# Amplifier.net
KiCad netlist of a schematic drawn in Altium Designer
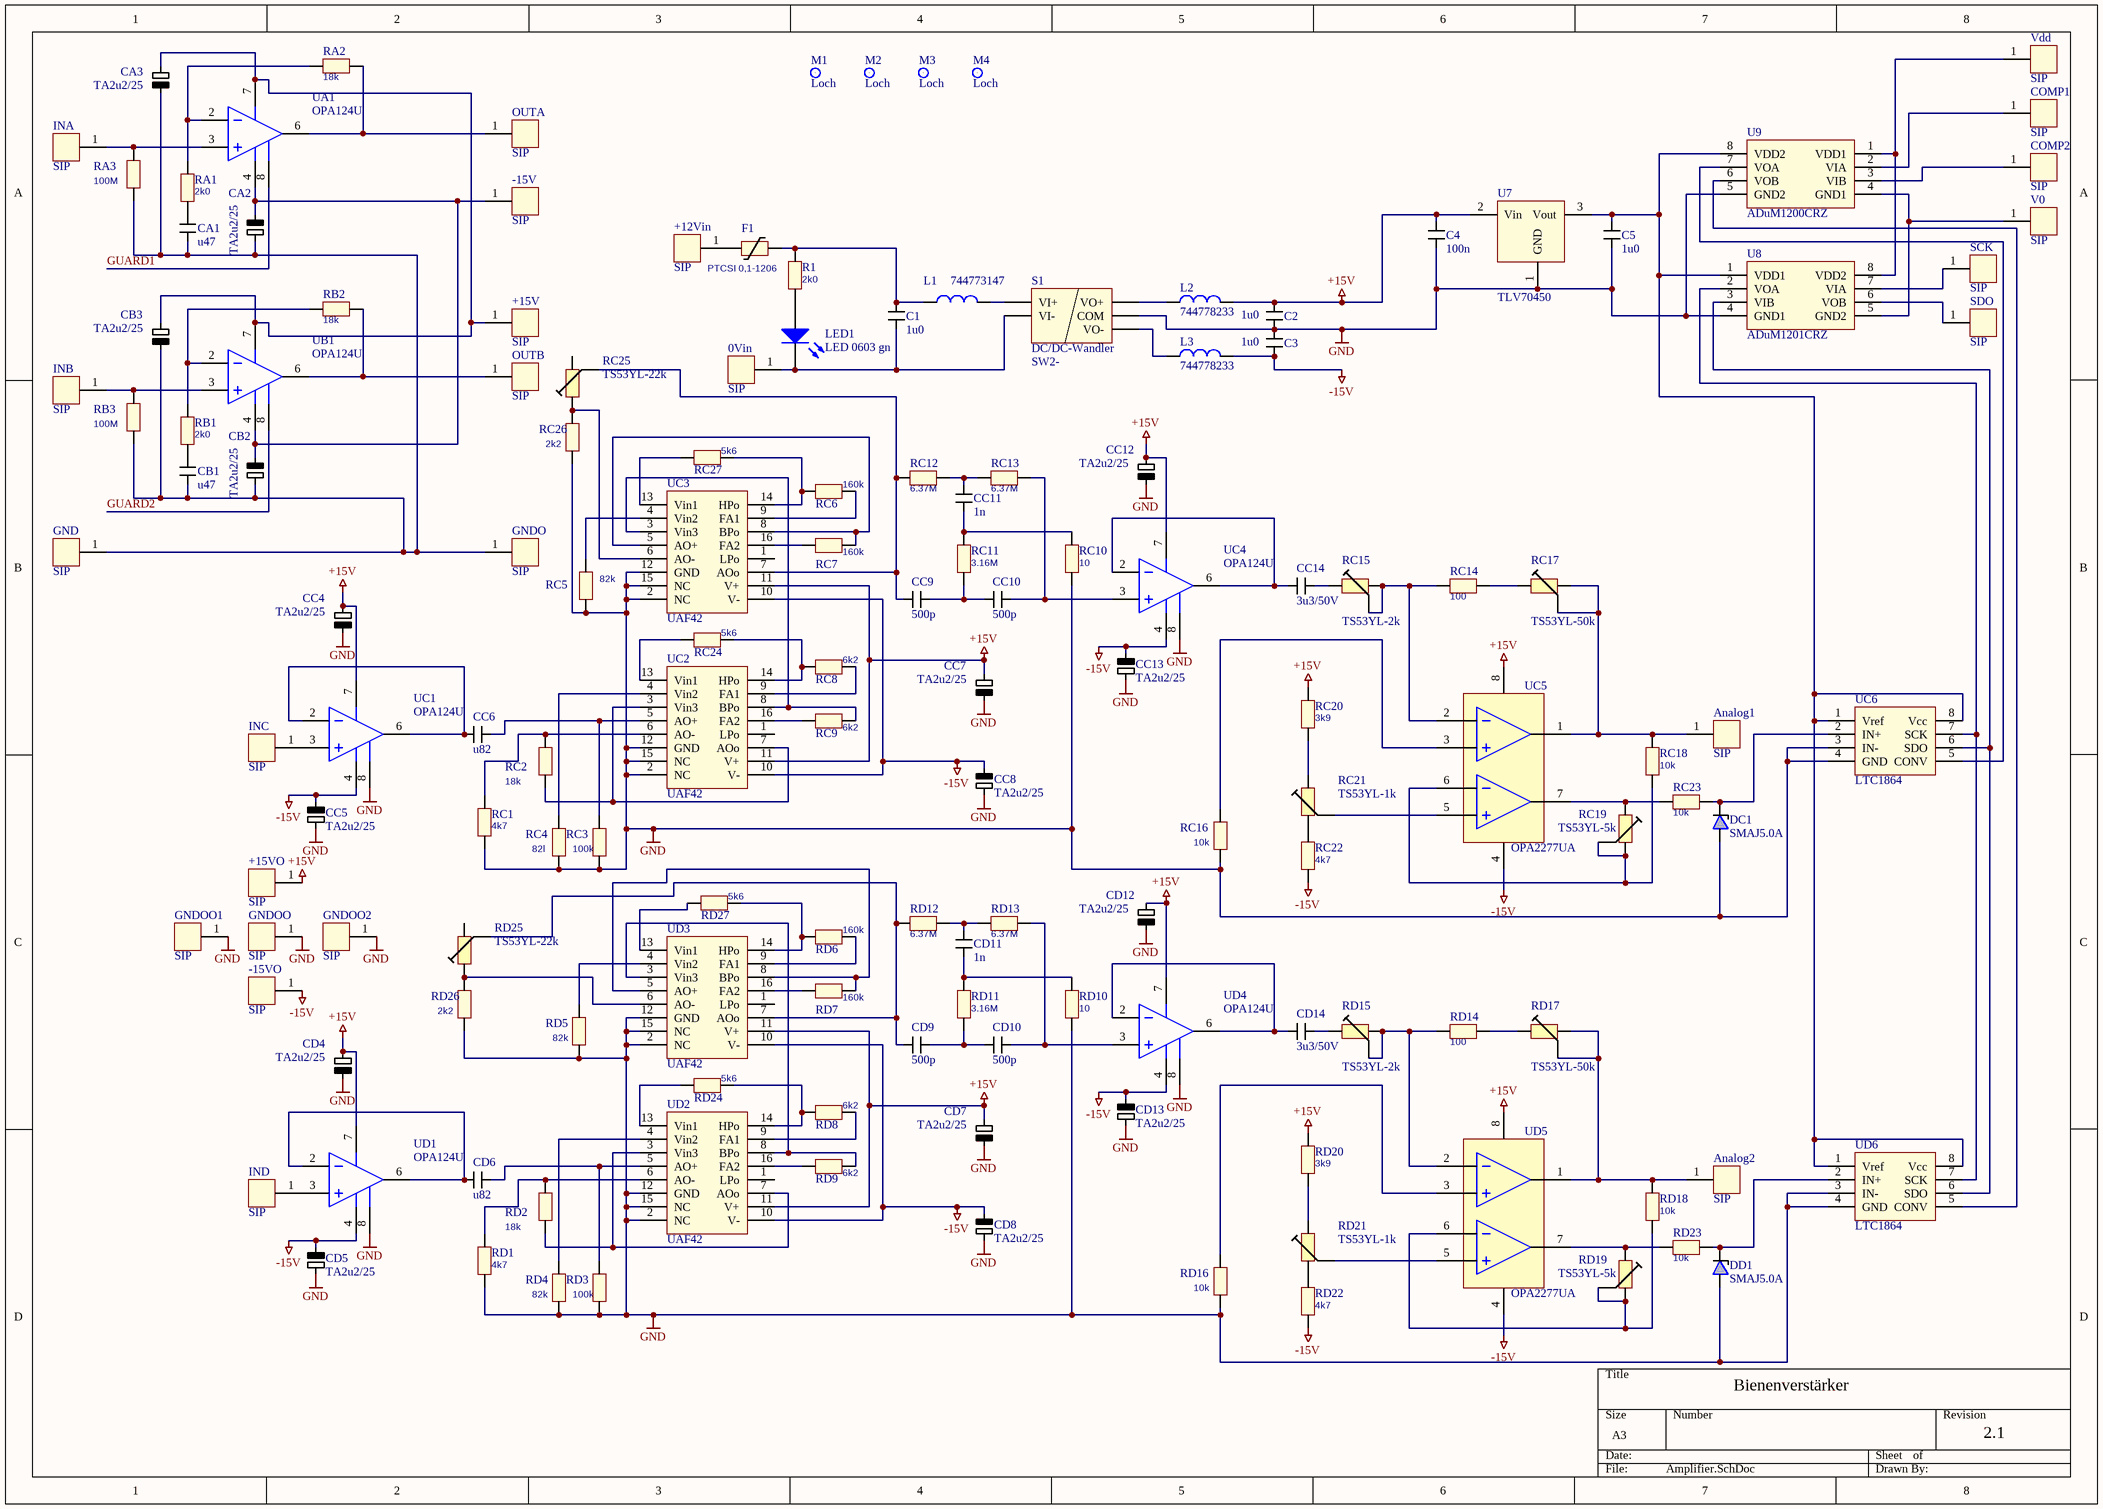
[diagram p0: Amplifier.SchDoc]

(export (version "E")
  (design (tool "Eeschema 10.0.6"))
  (components
    (comp (ref "+12Vin")
      (value "SIP")
      (footprint "PAD2,2x2,5")
      (description "2-pol. Leiste")
      (libsource (lib "") (part "SIP1_1"))
    )
    (comp (ref "+15V")
      (value "SIP")
      (footprint "PAD1X1")
      (description "2-pol. Leiste")
      (libsource (lib "GEP_EMech") (part "SIP1"))
    )
    (comp (ref "+15VO")
      (value "SIP")
      (footprint "PAD2,2x2,5")
      (description "2-pol. Leiste")
      (libsource (lib "") (part "SIP1_2"))
    )
    (comp (ref "-15V")
      (value "SIP")
      (footprint "PAD1X1")
      (description "2-pol. Leiste")
      (libsource (lib "GEP_EMech") (part "SIP1"))
    )
    (comp (ref "-15VO")
      (value "SIP")
      (footprint "PAD2,2x2,5")
      (description "2-pol. Leiste")
      (libsource (lib "") (part "SIP1_2"))
    )
    (comp (ref "0Vin")
      (value "SIP")
      (footprint "PAD2,2x2,5")
      (description "2-pol. Leiste")
      (libsource (lib "") (part "SIP1_1"))
    )
    (comp (ref "Analog1")
      (value "SIP")
      (footprint "PAD2,2x2,5")
      (description "2-pol. Leiste")
      (libsource (lib "GEP_EMech") (part "SIP1"))
    )
    (comp (ref "Analog2")
      (value "SIP")
      (footprint "PAD2,2x2,5")
      (description "2-pol. Leiste")
      (libsource (lib "GEP_EMech") (part "SIP1"))
    )
    (comp (ref "C1")
      (value "1u0")
      (footprint "0603")
      (description "Capacitor")
      (libsource (lib "GEP_Passiv") (part "Capacitor"))
    )
    (comp (ref "C2")
      (value "1u0")
      (footprint "0603")
      (description "Capacitor")
      (libsource (lib "GEP_Passiv") (part "Capacitor"))
    )
    (comp (ref "C3")
      (value "1u0")
      (footprint "0603")
      (description "Capacitor")
      (libsource (lib "GEP_Passiv") (part "Capacitor"))
    )
    (comp (ref "C4")
      (value "100n")
      (footprint "0603")
      (description "Capacitor")
      (libsource (lib "GEP_Passiv") (part "Capacitor"))
    )
    (comp (ref "C5")
      (value "1u0")
      (footprint "0603")
      (description "Capacitor")
      (libsource (lib "GEP_Passiv") (part "Capacitor"))
    )
    (comp (ref "CA1")
      (value "u47")
      (footprint "0603")
      (description "Capacitor")
      (libsource (lib "GEP_Passiv") (part "Capacitor"))
    )
    (comp (ref "CA2")
      (value "TA2u2/25")
      (footprint "TA_SMD-A")
      (description "Elko")
      (libsource (lib "GEP_Passiv") (part "Elko"))
    )
    (comp (ref "CA3")
      (value "TA2u2/25")
      (footprint "TA_SMD-A")
      (description "Elko")
      (libsource (lib "") (part "Elko_1"))
    )
    (comp (ref "CB1")
      (value "u47")
      (footprint "0603")
      (description "Capacitor")
      (libsource (lib "GEP_Passiv") (part "Capacitor"))
    )
    (comp (ref "CB2")
      (value "TA2u2/25")
      (footprint "TA_SMD-A")
      (description "Elko")
      (libsource (lib "GEP_Passiv") (part "Elko"))
    )
    (comp (ref "CB3")
      (value "TA2u2/25")
      (footprint "TA_SMD-A")
      (description "Elko")
      (libsource (lib "") (part "Elko_1"))
    )
    (comp (ref "CC4")
      (value "TA2u2/25")
      (footprint "TA_SMD-A")
      (description "Elko")
      (libsource (lib "") (part "Elko_1"))
    )
    (comp (ref "CC5")
      (value "TA2u2/25")
      (footprint "TA_SMD-A")
      (description "Elko")
      (libsource (lib "GEP_Passiv") (part "Elko"))
    )
    (comp (ref "CC6")
      (value "u82")
      (footprint "C0805")
      (description "Capacitor")
      (libsource (lib "GEP_Passiv") (part "Capacitor"))
    )
    (comp (ref "CC7")
      (value "TA2u2/25")
      (footprint "TA_SMD-A")
      (description "Elko")
      (libsource (lib "") (part "Elko_1"))
    )
    (comp (ref "CC8")
      (value "TA2u2/25")
      (footprint "TA_SMD-A")
      (description "Elko")
      (libsource (lib "GEP_Passiv") (part "Elko"))
    )
    (comp (ref "CC9")
      (value "500p")
      (footprint "0603")
      (description "Capacitor")
      (libsource (lib "GEP_Passiv") (part "Capacitor"))
    )
    (comp (ref "CC10")
      (value "500p")
      (footprint "0603")
      (description "Capacitor")
      (libsource (lib "GEP_Passiv") (part "Capacitor"))
    )
    (comp (ref "CC11")
      (value "1n")
      (footprint "0603")
      (description "Capacitor")
      (libsource (lib "GEP_Passiv") (part "Capacitor"))
    )
    (comp (ref "CC12")
      (value "TA2u2/25")
      (footprint "TA_SMD-A")
      (description "Elko")
      (libsource (lib "") (part "Elko_1"))
    )
    (comp (ref "CC13")
      (value "TA2u2/25")
      (footprint "TA_SMD-A")
      (description "Elko")
      (libsource (lib "GEP_Passiv") (part "Elko"))
    )
    (comp (ref "CC14")
      (value "3u3/50V")
      (footprint "1206")
      (description "Capacitor")
      (libsource (lib "GEP_Passiv") (part "Capacitor"))
    )
    (comp (ref "CD4")
      (value "TA2u2/25")
      (footprint "TA_SMD-A")
      (description "Elko")
      (libsource (lib "") (part "Elko_1"))
    )
    (comp (ref "CD5")
      (value "TA2u2/25")
      (footprint "TA_SMD-A")
      (description "Elko")
      (libsource (lib "GEP_Passiv") (part "Elko"))
    )
    (comp (ref "CD6")
      (value "u82")
      (footprint "C0805")
      (description "Capacitor")
      (libsource (lib "GEP_Passiv") (part "Capacitor"))
    )
    (comp (ref "CD7")
      (value "TA2u2/25")
      (footprint "TA_SMD-A")
      (description "Elko")
      (libsource (lib "") (part "Elko_1"))
    )
    (comp (ref "CD8")
      (value "TA2u2/25")
      (footprint "TA_SMD-A")
      (description "Elko")
      (libsource (lib "GEP_Passiv") (part "Elko"))
    )
    (comp (ref "CD9")
      (value "500p")
      (footprint "0603")
      (description "Capacitor")
      (libsource (lib "GEP_Passiv") (part "Capacitor"))
    )
    (comp (ref "CD10")
      (value "500p")
      (footprint "0603")
      (description "Capacitor")
      (libsource (lib "GEP_Passiv") (part "Capacitor"))
    )
    (comp (ref "CD11")
      (value "1n")
      (footprint "0603")
      (description "Capacitor")
      (libsource (lib "GEP_Passiv") (part "Capacitor"))
    )
    (comp (ref "CD12")
      (value "TA2u2/25")
      (footprint "TA_SMD-A")
      (description "Elko")
      (libsource (lib "") (part "Elko_1"))
    )
    (comp (ref "CD13")
      (value "TA2u2/25")
      (footprint "TA_SMD-A")
      (description "Elko")
      (libsource (lib "GEP_Passiv") (part "Elko"))
    )
    (comp (ref "CD14")
      (value "3u3/50V")
      (footprint "1206")
      (description "Capacitor")
      (libsource (lib "GEP_Passiv") (part "Capacitor"))
    )
    (comp (ref "COMP1")
      (value "SIP")
      (footprint "PAD2,2x2,5")
      (description "2-pol. Leiste")
      (libsource (lib "GEP_EMech") (part "SIP1"))
    )
    (comp (ref "COMP2")
      (value "SIP")
      (footprint "PAD2,2x2,5")
      (description "2-pol. Leiste")
      (libsource (lib "GEP_EMech") (part "SIP1"))
    )
    (comp (ref "DC1")
      (value "SMAJ5.0A")
      (footprint "SMA (DO214AC)")
      (description "DIODE TRANSIL")
      (libsource (lib "GEP_Discrete") (part "DIODE TRANSIL"))
    )
    (comp (ref "DD1")
      (value "SMAJ5.0A")
      (footprint "SMA (DO214AC)")
      (description "DIODE TRANSIL")
      (libsource (lib "GEP_Discrete") (part "DIODE TRANSIL"))
    )
    (comp (ref "F1")
      (value "PTCSI 0,1-1206")
      (footprint "1206")
      (description "Multifuse")
      (libsource (lib "GEP_Passiv") (part "Multifuse"))
    )
    (comp (ref "GND")
      (value "SIP")
      (footprint "PAD1X1")
      (description "2-pol. Leiste")
      (libsource (lib "") (part "SIP1_2"))
    )
    (comp (ref "GNDO")
      (value "SIP")
      (footprint "PAD1X1")
      (description "2-pol. Leiste")
      (libsource (lib "GEP_EMech") (part "SIP1"))
    )
    (comp (ref "GNDOO")
      (value "SIP")
      (footprint "PAD2,2x2,5")
      (description "2-pol. Leiste")
      (libsource (lib "") (part "SIP1_2"))
    )
    (comp (ref "GNDOO1")
      (value "SIP")
      (footprint "PAD2,2x2,5")
      (description "2-pol. Leiste")
      (libsource (lib "") (part "SIP1_2"))
    )
    (comp (ref "GNDOO2")
      (value "SIP")
      (footprint "PAD2,2x2,5")
      (description "2-pol. Leiste")
      (libsource (lib "") (part "SIP1_2"))
    )
    (comp (ref "INA")
      (value "SIP")
      (footprint "PAD1X1")
      (description "2-pol. Leiste")
      (libsource (lib "") (part "SIP1_2"))
    )
    (comp (ref "INB")
      (value "SIP")
      (footprint "PAD1X1")
      (description "2-pol. Leiste")
      (libsource (lib "") (part "SIP1_2"))
    )
    (comp (ref "INC")
      (value "SIP")
      (footprint "PAD2,2x2,5")
      (description "2-pol. Leiste")
      (libsource (lib "") (part "SIP1_2"))
    )
    (comp (ref "IND")
      (value "SIP")
      (footprint "PAD2,2x2,5")
      (description "2-pol. Leiste")
      (libsource (lib "") (part "SIP1_2"))
    )
    (comp (ref "L1")
      (value "744773147")
      (footprint "WE-4045")
      (description "Inductor")
      (libsource (lib "GEP_Passiv") (part "Inductor"))
    )
    (comp (ref "L2")
      (value "744778233")
      (footprint "WE-PD S/M/XS")
      (description "Inductor")
      (libsource (lib "GEP_Passiv") (part "Inductor"))
    )
    (comp (ref "L3")
      (value "744778233")
      (footprint "WE-PD S/M/XS")
      (description "Inductor")
      (libsource (lib "GEP_Passiv") (part "Inductor"))
    )
    (comp (ref "LED1")
      (value "LED 0603 gn")
      (footprint "0603-Diode")
      (description "Typical RED, GREEN, YELLOW, AMBER GaAs LED")
      (fields (field (name "PUBLISHER") "Altium Limited"))
      (libsource (lib "GEP_Opto") (part "LED"))
    )
    (comp (ref "M1")
      (value "Loch")
      (footprint "MTHoleM3")
      (description "Befestigungsloch M3")
      (fields (field (name "Comment") "MThole"))
      (libsource (lib "GEP_EMech") (part "MTHoleM3"))
    )
    (comp (ref "M2")
      (value "Loch")
      (footprint "MTHoleM3")
      (description "Befestigungsloch M3")
      (fields (field (name "Comment") "MThole"))
      (libsource (lib "GEP_EMech") (part "MTHoleM3"))
    )
    (comp (ref "M3")
      (value "Loch")
      (footprint "MTHoleM3")
      (description "Befestigungsloch M3")
      (fields (field (name "Comment") "MThole"))
      (libsource (lib "GEP_EMech") (part "MTHoleM3"))
    )
    (comp (ref "M4")
      (value "Loch")
      (footprint "MTHoleM3")
      (description "Befestigungsloch M3")
      (fields (field (name "Comment") "MThole"))
      (libsource (lib "GEP_EMech") (part "MTHoleM3"))
    )
    (comp (ref "OUTA")
      (value "SIP")
      (footprint "PAD1X1")
      (description "2-pol. Leiste")
      (libsource (lib "GEP_EMech") (part "SIP1"))
    )
    (comp (ref "OUTB")
      (value "SIP")
      (footprint "PAD1X1")
      (description "2-pol. Leiste")
      (libsource (lib "GEP_EMech") (part "SIP1"))
    )
    (comp (ref "R1")
      (value "2k0")
      (footprint "0603")
      (description "Resistor")
      (libsource (lib "") (part "Resistor_1"))
    )
    (comp (ref "RA1")
      (value "2k0")
      (footprint "0603")
      (description "Resistor")
      (libsource (lib "") (part "Resistor_1"))
    )
    (comp (ref "RA2")
      (value "18k")
      (footprint "0603")
      (description "Resistor")
      (libsource (lib "") (part "Resistor_3"))
    )
    (comp (ref "RA3")
      (value "100M")
      (footprint "0603")
      (description "Resistor")
      (libsource (lib "") (part "Resistor_1"))
    )
    (comp (ref "RB1")
      (value "2k0")
      (footprint "0603")
      (description "Resistor")
      (libsource (lib "") (part "Resistor_1"))
    )
    (comp (ref "RB2")
      (value "18k")
      (footprint "0603")
      (description "Resistor")
      (libsource (lib "") (part "Resistor_3"))
    )
    (comp (ref "RB3")
      (value "100M")
      (footprint "0603")
      (description "Resistor")
      (libsource (lib "") (part "Resistor_1"))
    )
    (comp (ref "RC1")
      (value "4k7")
      (footprint "0603")
      (description "Resistor")
      (libsource (lib "") (part "Resistor_1"))
    )
    (comp (ref "RC2")
      (value "18k")
      (footprint "0603")
      (description "Resistor")
      (libsource (lib "") (part "Resistor_1"))
    )
    (comp (ref "RC3")
      (value "100k")
      (footprint "0603")
      (description "Resistor")
      (libsource (lib "") (part "Resistor_1"))
    )
    (comp (ref "RC4")
      (value "82l")
      (footprint "0603")
      (description "Resistor")
      (libsource (lib "") (part "Resistor_1"))
    )
    (comp (ref "RC5")
      (value "82k")
      (footprint "0603")
      (description "Resistor")
      (libsource (lib "") (part "Resistor_1"))
    )
    (comp (ref "RC6")
      (value "160k")
      (footprint "0603")
      (description "Resistor")
      (libsource (lib "GEP_Passiv") (part "Resistor"))
    )
    (comp (ref "RC7")
      (value "160k")
      (footprint "0603")
      (description "Resistor")
      (libsource (lib "GEP_Passiv") (part "Resistor"))
    )
    (comp (ref "RC8")
      (value "6k2")
      (footprint "0603")
      (description "Resistor")
      (libsource (lib "GEP_Passiv") (part "Resistor"))
    )
    (comp (ref "RC9")
      (value "6k2")
      (footprint "0603")
      (description "Resistor")
      (libsource (lib "GEP_Passiv") (part "Resistor"))
    )
    (comp (ref "RC10")
      (value "10")
      (footprint "0603")
      (description "Resistor")
      (libsource (lib "") (part "Resistor_1"))
    )
    (comp (ref "RC11")
      (value "3.16M")
      (footprint "0603")
      (description "Resistor")
      (libsource (lib "") (part "Resistor_1"))
    )
    (comp (ref "RC12")
      (value "6.37M")
      (footprint "0603")
      (description "Resistor")
      (libsource (lib "GEP_Passiv") (part "Resistor"))
    )
    (comp (ref "RC13")
      (value "6.37M")
      (footprint "0603")
      (description "Resistor")
      (libsource (lib "GEP_Passiv") (part "Resistor"))
    )
    (comp (ref "RC14")
      (value "100")
      (footprint "0603")
      (description "Resistor")
      (libsource (lib "GEP_Passiv") (part "Resistor"))
    )
    (comp (ref "RC15")
      (value "TS53YL-2k")
      (footprint "TS53YL")
      (description "Trimmer")
      (libsource (lib "GEP_Passiv") (part "Trimmer"))
    )
    (comp (ref "RC16")
      (value "10k")
      (footprint "0603")
      (description "Resistor")
      (libsource (lib "") (part "Resistor_1"))
    )
    (comp (ref "RC17")
      (value "TS53YL-50k")
      (footprint "TS53YL")
      (description "Trimmer")
      (libsource (lib "GEP_Passiv") (part "Trimmer"))
    )
    (comp (ref "RC18")
      (value "10k")
      (footprint "0603")
      (description "Resistor")
      (libsource (lib "") (part "Resistor_2"))
    )
    (comp (ref "RC19")
      (value "TS53YL-5k")
      (footprint "TS53YL")
      (description "Trimmer")
      (libsource (lib "") (part "Trimmer_2"))
    )
    (comp (ref "RC20")
      (value "3k9")
      (footprint "0603")
      (description "Resistor")
      (libsource (lib "") (part "Resistor_2"))
    )
    (comp (ref "RC21")
      (value "TS53YL-1k")
      (footprint "TS53YL")
      (description "Trimmer")
      (libsource (lib "") (part "Trimmer_1"))
    )
    (comp (ref "RC22")
      (value "4k7")
      (footprint "0603")
      (description "Resistor")
      (libsource (lib "") (part "Resistor_2"))
    )
    (comp (ref "RC23")
      (value "10k")
      (footprint "0603")
      (description "Resistor")
      (libsource (lib "") (part "Resistor_3"))
    )
    (comp (ref "RC24")
      (value "5k6")
      (footprint "0603")
      (description "Resistor")
      (libsource (lib "GEP_Passiv") (part "Resistor"))
    )
    (comp (ref "RC25")
      (value "TS53YL-22k")
      (footprint "TS53YL")
      (description "Trimmer")
      (libsource (lib "") (part "Trimmer_3"))
    )
    (comp (ref "RC26")
      (value "2k2")
      (footprint "0603")
      (description "Resistor")
      (libsource (lib "") (part "Resistor_1"))
    )
    (comp (ref "RC27")
      (value "5k6")
      (footprint "0603")
      (description "Resistor")
      (libsource (lib "GEP_Passiv") (part "Resistor"))
    )
    (comp (ref "RD1")
      (value "4k7")
      (footprint "0603")
      (description "Resistor")
      (libsource (lib "") (part "Resistor_1"))
    )
    (comp (ref "RD2")
      (value "18k")
      (footprint "0603")
      (description "Resistor")
      (libsource (lib "") (part "Resistor_1"))
    )
    (comp (ref "RD3")
      (value "100k")
      (footprint "0603")
      (description "Resistor")
      (libsource (lib "") (part "Resistor_1"))
    )
    (comp (ref "RD4")
      (value "82k")
      (footprint "0603")
      (description "Resistor")
      (libsource (lib "") (part "Resistor_1"))
    )
    (comp (ref "RD5")
      (value "82k")
      (footprint "0603")
      (description "Resistor")
      (libsource (lib "") (part "Resistor_1"))
    )
    (comp (ref "RD6")
      (value "160k")
      (footprint "0603")
      (description "Resistor")
      (libsource (lib "GEP_Passiv") (part "Resistor"))
    )
    (comp (ref "RD7")
      (value "160k")
      (footprint "0603")
      (description "Resistor")
      (libsource (lib "GEP_Passiv") (part "Resistor"))
    )
    (comp (ref "RD8")
      (value "6k2")
      (footprint "0603")
      (description "Resistor")
      (libsource (lib "GEP_Passiv") (part "Resistor"))
    )
    (comp (ref "RD9")
      (value "6k2")
      (footprint "0603")
      (description "Resistor")
      (libsource (lib "GEP_Passiv") (part "Resistor"))
    )
    (comp (ref "RD10")
      (value "10")
      (footprint "0603")
      (description "Resistor")
      (libsource (lib "") (part "Resistor_1"))
    )
    (comp (ref "RD11")
      (value "3.16M")
      (footprint "0603")
      (description "Resistor")
      (libsource (lib "") (part "Resistor_1"))
    )
    (comp (ref "RD12")
      (value "6.37M")
      (footprint "0603")
      (description "Resistor")
      (libsource (lib "GEP_Passiv") (part "Resistor"))
    )
    (comp (ref "RD13")
      (value "6.37M")
      (footprint "0603")
      (description "Resistor")
      (libsource (lib "GEP_Passiv") (part "Resistor"))
    )
    (comp (ref "RD14")
      (value "100")
      (footprint "0603")
      (description "Resistor")
      (libsource (lib "GEP_Passiv") (part "Resistor"))
    )
    (comp (ref "RD15")
      (value "TS53YL-2k")
      (footprint "TS53YL")
      (description "Trimmer")
      (libsource (lib "GEP_Passiv") (part "Trimmer"))
    )
    (comp (ref "RD16")
      (value "10k")
      (footprint "0603")
      (description "Resistor")
      (libsource (lib "") (part "Resistor_1"))
    )
    (comp (ref "RD17")
      (value "TS53YL-50k")
      (footprint "TS53YL")
      (description "Trimmer")
      (libsource (lib "GEP_Passiv") (part "Trimmer"))
    )
    (comp (ref "RD18")
      (value "10k")
      (footprint "0603")
      (description "Resistor")
      (libsource (lib "") (part "Resistor_2"))
    )
    (comp (ref "RD19")
      (value "TS53YL-5k")
      (footprint "TS53YL")
      (description "Trimmer")
      (libsource (lib "") (part "Trimmer_2"))
    )
    (comp (ref "RD20")
      (value "3k9")
      (footprint "0603")
      (description "Resistor")
      (libsource (lib "") (part "Resistor_2"))
    )
    (comp (ref "RD21")
      (value "TS53YL-1k")
      (footprint "TS53YL")
      (description "Trimmer")
      (libsource (lib "") (part "Trimmer_1"))
    )
    (comp (ref "RD22")
      (value "4k7")
      (footprint "0603")
      (description "Resistor")
      (libsource (lib "") (part "Resistor_2"))
    )
    (comp (ref "RD23")
      (value "10k")
      (footprint "0603")
      (description "Resistor")
      (libsource (lib "") (part "Resistor_3"))
    )
    (comp (ref "RD24")
      (value "5k6")
      (footprint "0603")
      (description "Resistor")
      (libsource (lib "GEP_Passiv") (part "Resistor"))
    )
    (comp (ref "RD25")
      (value "TS53YL-22k")
      (footprint "TS53YL")
      (description "Trimmer")
      (libsource (lib "") (part "Trimmer_3"))
    )
    (comp (ref "RD26")
      (value "2k2")
      (footprint "0603")
      (description "Resistor")
      (libsource (lib "") (part "Resistor_1"))
    )
    (comp (ref "RD27")
      (value "5k6")
      (footprint "0603")
      (description "Resistor")
      (libsource (lib "GEP_Passiv") (part "Resistor"))
    )
    (comp (ref "S1")
      (value "DC/DC-Wandler")
      (footprint "DC/DC 2W Dual")
      (description "DC/DC-Wandler Dual output")
      (fields (field (name "ALTIUM_VALUE") "SW2-"))
      (libsource (lib "GEP_ICs") (part "DC/DC dual"))
    )
    (comp (ref "SCK")
      (value "SIP")
      (footprint "PAD2,2x2,5")
      (description "2-pol. Leiste")
      (libsource (lib "GEP_EMech") (part "SIP1"))
    )
    (comp (ref "SDO")
      (value "SIP")
      (footprint "PAD2,2x2,5")
      (description "2-pol. Leiste")
      (libsource (lib "GEP_EMech") (part "SIP1"))
    )
    (comp (ref "U7")
      (value "TLV70450")
      (footprint "SOT23/5")
      (description "VReg GND-IN_OUT")
      (libsource (lib "GEP_ICs") (part "TLV704xx"))
    )
    (comp (ref "U8")
      (value "ADuM1201CRZ")
      (footprint "SO8")
      (libsource (lib "GEP_ICs") (part "ADuM1201/3211"))
    )
    (comp (ref "U9") (value "ADuM1200CRZ") (footprint "SO8") (libsource (lib "GEP_ICs") (part "ADuM1200")))
    (comp (ref "UA1")
      (value "OPA124U")
      (footprint "SO8")
      (description "Single General-Purpose, Low-Voltage Rail-to-Rail Output Operational Amplifier")
      (libsource (lib "GEP_ICs") (part "OPA124U"))
    )
    (comp (ref "UB1")
      (value "OPA124U")
      (footprint "SO8")
      (description "Single General-Purpose, Low-Voltage Rail-to-Rail Output Operational Amplifier")
      (libsource (lib "GEP_ICs") (part "OPA124U"))
    )
    (comp (ref "UC1")
      (value "OPA124U")
      (footprint "SO8")
      (description "Single General-Purpose, Low-Voltage Rail-to-Rail Output Operational Amplifier")
      (libsource (lib "GEP_ICs") (part "OPA124U"))
    )
    (comp (ref "UC2") (value "UAF42") (footprint "SO16W") (libsource (lib "GEP_ICs") (part "UAF42")))
    (comp (ref "UC3") (value "UAF42") (footprint "SO16W") (libsource (lib "GEP_ICs") (part "UAF42")))
    (comp (ref "UC4")
      (value "OPA124U")
      (footprint "SO8")
      (description "Single General-Purpose, Low-Voltage Rail-to-Rail Output Operational Amplifier")
      (libsource (lib "GEP_ICs") (part "OPA124U"))
    )
    (comp (ref "UC5")
      (value "OPA2277UA")
      (footprint "SO8")
      (description "Single General-Purpose, Low-Voltage Rail-to-Rail Output Operational Amplifier")
      (fields (field (name "Comment") "OPA2277"))
      (libsource (lib "GEP_ICs") (part "LTC6244"))
    )
    (comp (ref "UC6") (value "LTC1864") (footprint "SO8") (libsource (lib "GEP_ICs") (part "LTC1864")))
    (comp (ref "UD1")
      (value "OPA124U")
      (footprint "SO8")
      (description "Single General-Purpose, Low-Voltage Rail-to-Rail Output Operational Amplifier")
      (libsource (lib "GEP_ICs") (part "OPA124U"))
    )
    (comp (ref "UD2") (value "UAF42") (footprint "SO16W") (libsource (lib "GEP_ICs") (part "UAF42")))
    (comp (ref "UD3") (value "UAF42") (footprint "SO16W") (libsource (lib "GEP_ICs") (part "UAF42")))
    (comp (ref "UD4")
      (value "OPA124U")
      (footprint "SO8")
      (description "Single General-Purpose, Low-Voltage Rail-to-Rail Output Operational Amplifier")
      (libsource (lib "GEP_ICs") (part "OPA124U"))
    )
    (comp (ref "UD5")
      (value "OPA2277UA")
      (footprint "SO8")
      (description "Single General-Purpose, Low-Voltage Rail-to-Rail Output Operational Amplifier")
      (fields (field (name "Comment") "OPA2277"))
      (libsource (lib "GEP_ICs") (part "LTC6244"))
    )
    (comp (ref "UD6") (value "LTC1864") (footprint "SO8") (libsource (lib "GEP_ICs") (part "LTC1864")))
    (comp (ref "V0")
      (value "SIP")
      (footprint "PAD2,2x2,5")
      (description "2-pol. Leiste")
      (libsource (lib "GEP_EMech") (part "SIP1"))
    )
    (comp (ref "Vdd")
      (value "SIP")
      (footprint "PAD2,2x2,5")
      (description "2-pol. Leiste")
      (libsource (lib "GEP_EMech") (part "SIP1"))
    )
  )
  (nets
    (net (code "1") (name "+15V") (class "Default")
      (node (ref "+15VO") (pin "1") (pinfunction "1_1") (pintype "passive"))
      (node (ref "C2") (pin "2") (pinfunction "2_2") (pintype "passive"))
      (node (ref "C4") (pin "2") (pinfunction "2_2") (pintype "passive"))
      (node (ref "CC12") (pin "A") (pinfunction "1_A") (pintype "passive"))
      (node (ref "CC4") (pin "A") (pinfunction "1_A") (pintype "passive"))
      (node (ref "CC7") (pin "A") (pinfunction "1_A") (pintype "passive"))
      (node (ref "CD12") (pin "A") (pinfunction "1_A") (pintype "passive"))
      (node (ref "CD4") (pin "A") (pinfunction "1_A") (pintype "passive"))
      (node (ref "CD7") (pin "A") (pinfunction "1_A") (pintype "passive"))
      (node (ref "L2") (pin "2") (pinfunction "2_2") (pintype "passive"))
      (node (ref "RC20") (pin "1") (pinfunction "1_1") (pintype "passive"))
      (node (ref "RD20") (pin "1") (pinfunction "1_1") (pintype "passive"))
      (node (ref "U7") (pin "2") (pinfunction "Vin_2") (pintype "passive"))
      (node (ref "UC1") (pin "7") (pinfunction "V+_7") (pintype "power_in"))
      (node (ref "UC2") (pin "11") (pinfunction "V+_11") (pintype "passive"))
      (node (ref "UC3") (pin "11") (pinfunction "V+_11") (pintype "passive"))
      (node (ref "UC4") (pin "7") (pinfunction "V+_7") (pintype "power_in"))
      (node (ref "UC5") (pin "8") (pinfunction "V+_8") (pintype "power_in"))
      (node (ref "UD1") (pin "7") (pinfunction "V+_7") (pintype "power_in"))
      (node (ref "UD2") (pin "11") (pinfunction "V+_11") (pintype "passive"))
      (node (ref "UD3") (pin "11") (pinfunction "V+_11") (pintype "passive"))
      (node (ref "UD4") (pin "7") (pinfunction "V+_7") (pintype "power_in"))
      (node (ref "UD5") (pin "8") (pinfunction "V+_8") (pintype "power_in"))
    )
    (net (code "2") (name "-15V") (class "Default")
      (node (ref "-15VO") (pin "1") (pinfunction "1_1") (pintype "passive"))
      (node (ref "C3") (pin "1") (pinfunction "1_1") (pintype "passive"))
      (node (ref "CC13") (pin "C") (pinfunction "2_C") (pintype "passive"))
      (node (ref "CC5") (pin "C") (pinfunction "2_C") (pintype "passive"))
      (node (ref "CC8") (pin "C") (pinfunction "2_C") (pintype "passive"))
      (node (ref "CD13") (pin "C") (pinfunction "2_C") (pintype "passive"))
      (node (ref "CD5") (pin "C") (pinfunction "2_C") (pintype "passive"))
      (node (ref "CD8") (pin "C") (pinfunction "2_C") (pintype "passive"))
      (node (ref "L3") (pin "2") (pinfunction "2_2") (pintype "passive"))
      (node (ref "RC22") (pin "2") (pinfunction "2_2") (pintype "passive"))
      (node (ref "RD22") (pin "2") (pinfunction "2_2") (pintype "passive"))
      (node (ref "UC1") (pin "4") (pinfunction "V-_4") (pintype "power_in"))
      (node (ref "UC2") (pin "10") (pinfunction "V-_10") (pintype "passive"))
      (node (ref "UC3") (pin "10") (pinfunction "V-_10") (pintype "passive"))
      (node (ref "UC4") (pin "4") (pinfunction "V-_4") (pintype "power_in"))
      (node (ref "UC5") (pin "4") (pinfunction "V-_4") (pintype "power_in"))
      (node (ref "UD1") (pin "4") (pinfunction "V-_4") (pintype "power_in"))
      (node (ref "UD2") (pin "10") (pinfunction "V-_10") (pintype "passive"))
      (node (ref "UD3") (pin "10") (pinfunction "V-_10") (pintype "passive"))
      (node (ref "UD4") (pin "4") (pinfunction "V-_4") (pintype "power_in"))
      (node (ref "UD5") (pin "4") (pinfunction "V-_4") (pintype "power_in"))
    )
    (net (code "3") (name "/GUARD1") (class "Default")
      (node (ref "UA1") (pin "8") (pinfunction "Sub_8") (pintype "passive"))
    )
    (net (code "4") (name "/GUARD2") (class "Default")
      (node (ref "UB1") (pin "8") (pinfunction "Sub_8") (pintype "passive"))
    )
    (net (code "5") (name "GND") (class "Default")
      (node (ref "C2") (pin "1") (pinfunction "1_1") (pintype "passive"))
      (node (ref "C3") (pin "2") (pinfunction "2_2") (pintype "passive"))
      (node (ref "C4") (pin "1") (pinfunction "1_1") (pintype "passive"))
      (node (ref "C5") (pin "1") (pinfunction "1_1") (pintype "passive"))
      (node (ref "CC12") (pin "C") (pinfunction "2_C") (pintype "passive"))
      (node (ref "CC13") (pin "A") (pinfunction "1_A") (pintype "passive"))
      (node (ref "CC4") (pin "C") (pinfunction "2_C") (pintype "passive"))
      (node (ref "CC5") (pin "A") (pinfunction "1_A") (pintype "passive"))
      (node (ref "CC7") (pin "C") (pinfunction "2_C") (pintype "passive"))
      (node (ref "CC8") (pin "A") (pinfunction "1_A") (pintype "passive"))
      (node (ref "CD12") (pin "C") (pinfunction "2_C") (pintype "passive"))
      (node (ref "CD13") (pin "A") (pinfunction "1_A") (pintype "passive"))
      (node (ref "CD4") (pin "C") (pinfunction "2_C") (pintype "passive"))
      (node (ref "CD5") (pin "A") (pinfunction "1_A") (pintype "passive"))
      (node (ref "CD7") (pin "C") (pinfunction "2_C") (pintype "passive"))
      (node (ref "CD8") (pin "A") (pinfunction "1_A") (pintype "passive"))
      (node (ref "DC1") (pin "A") (pinfunction "A_A") (pintype "passive"))
      (node (ref "DD1") (pin "A") (pinfunction "A_A") (pintype "passive"))
      (node (ref "GNDOO") (pin "1") (pinfunction "1_1") (pintype "passive"))
      (node (ref "GNDOO1") (pin "1") (pinfunction "1_1") (pintype "passive"))
      (node (ref "GNDOO2") (pin "1") (pinfunction "1_1") (pintype "passive"))
      (node (ref "RC1") (pin "1") (pinfunction "1_1") (pintype "passive"))
      (node (ref "RC10") (pin "1") (pinfunction "1_1") (pintype "passive"))
      (node (ref "RC16") (pin "1") (pinfunction "1_1") (pintype "passive"))
      (node (ref "RC26") (pin "1") (pinfunction "1_1") (pintype "passive"))
      (node (ref "RC3") (pin "1") (pinfunction "1_1") (pintype "passive"))
      (node (ref "RC4") (pin "1") (pinfunction "1_1") (pintype "passive"))
      (node (ref "RC5") (pin "1") (pinfunction "1_1") (pintype "passive"))
      (node (ref "RD1") (pin "1") (pinfunction "1_1") (pintype "passive"))
      (node (ref "RD10") (pin "1") (pinfunction "1_1") (pintype "passive"))
      (node (ref "RD16") (pin "1") (pinfunction "1_1") (pintype "passive"))
      (node (ref "RD26") (pin "1") (pinfunction "1_1") (pintype "passive"))
      (node (ref "RD3") (pin "1") (pinfunction "1_1") (pintype "passive"))
      (node (ref "RD4") (pin "1") (pinfunction "1_1") (pintype "passive"))
      (node (ref "RD5") (pin "1") (pinfunction "1_1") (pintype "passive"))
      (node (ref "S1") (pin "COM") (pinfunction "COM_COM") (pintype "passive"))
      (node (ref "U7") (pin "1") (pinfunction "GND_1") (pintype "power_in"))
      (node (ref "U8") (pin "4") (pinfunction "GND1_4") (pintype "passive"))
      (node (ref "U9") (pin "5") (pinfunction "GND2_5") (pintype "passive"))
      (node (ref "UC1") (pin "8") (pinfunction "Sub_8") (pintype "passive"))
      (node (ref "UC2") (pin "12") (pinfunction "GND_12") (pintype "passive"))
      (node (ref "UC2") (pin "15") (pinfunction "NC_15") (pintype "passive"))
      (node (ref "UC2") (pin "2") (pinfunction "NC_2") (pintype "passive"))
      (node (ref "UC3") (pin "12") (pinfunction "GND_12") (pintype "passive"))
      (node (ref "UC3") (pin "15") (pinfunction "NC_15") (pintype "passive"))
      (node (ref "UC3") (pin "2") (pinfunction "NC_2") (pintype "passive"))
      (node (ref "UC4") (pin "8") (pinfunction "Sub_8") (pintype "passive"))
      (node (ref "UC6") (pin "3") (pinfunction "IN-_3") (pintype "passive"))
      (node (ref "UC6") (pin "4") (pinfunction "GND_4") (pintype "passive"))
      (node (ref "UD1") (pin "8") (pinfunction "Sub_8") (pintype "passive"))
      (node (ref "UD2") (pin "12") (pinfunction "GND_12") (pintype "passive"))
      (node (ref "UD2") (pin "15") (pinfunction "NC_15") (pintype "passive"))
      (node (ref "UD2") (pin "2") (pinfunction "NC_2") (pintype "passive"))
      (node (ref "UD3") (pin "12") (pinfunction "GND_12") (pintype "passive"))
      (node (ref "UD3") (pin "15") (pinfunction "NC_15") (pintype "passive"))
      (node (ref "UD3") (pin "2") (pinfunction "NC_2") (pintype "passive"))
      (node (ref "UD4") (pin "8") (pinfunction "Sub_8") (pintype "passive"))
      (node (ref "UD6") (pin "3") (pinfunction "IN-_3") (pintype "passive"))
      (node (ref "UD6") (pin "4") (pinfunction "GND_4") (pintype "passive"))
    )
    (net (code "6") (name "Net-(+12Vin-Pad1)") (class "Default")
      (node (ref "+12Vin") (pin "1") (pinfunction "1_1") (pintype "passive"))
      (node (ref "F1") (pin "1") (pinfunction "1_1") (pintype "passive"))
    )
    (net (code "7") (name "Net-(C1-Pad2)") (class "Default")
      (node (ref "C1") (pin "2") (pinfunction "2_2") (pintype "passive"))
      (node (ref "F1") (pin "2") (pinfunction "2_2") (pintype "passive"))
      (node (ref "L1") (pin "1") (pinfunction "1_1") (pintype "passive"))
      (node (ref "R1") (pin "2") (pinfunction "2_2") (pintype "passive"))
    )
    (net (code "8") (name "Net-(CA1-Pad2)") (class "Default")
      (node (ref "CA1") (pin "2") (pinfunction "2_2") (pintype "passive"))
      (node (ref "RA1") (pin "1") (pinfunction "1_1") (pintype "passive"))
    )
    (net (code "9") (name "Net-(CA2-1)") (class "Default")
      (node (ref "CA1") (pin "1") (pinfunction "1_1") (pintype "passive"))
      (node (ref "CA2") (pin "A") (pinfunction "1_A") (pintype "passive"))
      (node (ref "CA3") (pin "C") (pinfunction "2_C") (pintype "passive"))
      (node (ref "CB1") (pin "1") (pinfunction "1_1") (pintype "passive"))
      (node (ref "CB2") (pin "A") (pinfunction "1_A") (pintype "passive"))
      (node (ref "CB3") (pin "C") (pinfunction "2_C") (pintype "passive"))
      (node (ref "GND") (pin "1") (pinfunction "1_1") (pintype "passive"))
      (node (ref "GNDO") (pin "1") (pinfunction "1_1") (pintype "passive"))
      (node (ref "RA3") (pin "1") (pinfunction "1_1") (pintype "passive"))
      (node (ref "RB3") (pin "1") (pinfunction "1_1") (pintype "passive"))
    )
    (net (code "10") (name "Net-(CA2-2)") (class "Default")
      (node (ref "-15V") (pin "1") (pinfunction "1_1") (pintype "passive"))
      (node (ref "CA2") (pin "C") (pinfunction "2_C") (pintype "passive"))
      (node (ref "CB2") (pin "C") (pinfunction "2_C") (pintype "passive"))
      (node (ref "UA1") (pin "4") (pinfunction "V-_4") (pintype "power_in"))
      (node (ref "UB1") (pin "4") (pinfunction "V-_4") (pintype "power_in"))
    )
    (net (code "11") (name "Net-(CA3-1)") (class "Default")
      (node (ref "+15V") (pin "1") (pinfunction "1_1") (pintype "passive"))
      (node (ref "CA3") (pin "A") (pinfunction "1_A") (pintype "passive"))
      (node (ref "CB3") (pin "A") (pinfunction "1_A") (pintype "passive"))
      (node (ref "UA1") (pin "7") (pinfunction "V+_7") (pintype "power_in"))
      (node (ref "UB1") (pin "7") (pinfunction "V+_7") (pintype "power_in"))
    )
    (net (code "12") (name "Net-(CB1-Pad2)") (class "Default")
      (node (ref "CB1") (pin "2") (pinfunction "2_2") (pintype "passive"))
      (node (ref "RB1") (pin "1") (pinfunction "1_1") (pintype "passive"))
    )
    (net (code "13") (name "Net-(CC10-Pad1)") (class "Default")
      (node (ref "CC10") (pin "1") (pinfunction "1_1") (pintype "passive"))
      (node (ref "CC9") (pin "2") (pinfunction "2_2") (pintype "passive"))
      (node (ref "RC11") (pin "1") (pinfunction "1_1") (pintype "passive"))
    )
    (net (code "14") (name "Net-(CC11-Pad1)") (class "Default")
      (node (ref "CC11") (pin "1") (pinfunction "1_1") (pintype "passive"))
      (node (ref "RC10") (pin "2") (pinfunction "2_2") (pintype "passive"))
      (node (ref "RC11") (pin "2") (pinfunction "2_2") (pintype "passive"))
    )
    (net (code "15") (name "Net-(CC11-Pad2)") (class "Default")
      (node (ref "CC11") (pin "2") (pinfunction "2_2") (pintype "passive"))
      (node (ref "RC12") (pin "1") (pinfunction "1_1") (pintype "passive"))
      (node (ref "RC13") (pin "2") (pinfunction "2_2") (pintype "passive"))
    )
    (net (code "16") (name "Net-(CC14-Pad2)") (class "Default")
      (node (ref "CC14") (pin "2") (pinfunction "2_2") (pintype "passive"))
      (node (ref "RC15") (pin "1") (pinfunction "1_1") (pintype "passive"))
    )
    (net (code "17") (name "Net-(CD10-Pad1)") (class "Default")
      (node (ref "CD10") (pin "1") (pinfunction "1_1") (pintype "passive"))
      (node (ref "CD9") (pin "2") (pinfunction "2_2") (pintype "passive"))
      (node (ref "RD11") (pin "1") (pinfunction "1_1") (pintype "passive"))
    )
    (net (code "18") (name "Net-(CD11-Pad1)") (class "Default")
      (node (ref "CD11") (pin "1") (pinfunction "1_1") (pintype "passive"))
      (node (ref "RD10") (pin "2") (pinfunction "2_2") (pintype "passive"))
      (node (ref "RD11") (pin "2") (pinfunction "2_2") (pintype "passive"))
    )
    (net (code "19") (name "Net-(CD11-Pad2)") (class "Default")
      (node (ref "CD11") (pin "2") (pinfunction "2_2") (pintype "passive"))
      (node (ref "RD12") (pin "1") (pinfunction "1_1") (pintype "passive"))
      (node (ref "RD13") (pin "2") (pinfunction "2_2") (pintype "passive"))
    )
    (net (code "20") (name "Net-(CD14-Pad2)") (class "Default")
      (node (ref "CD14") (pin "2") (pinfunction "2_2") (pintype "passive"))
      (node (ref "RD15") (pin "1") (pinfunction "1_1") (pintype "passive"))
    )
    (net (code "21") (name "Net-(LED1-PadA)") (class "Default")
      (node (ref "LED1") (pin "A") (pinfunction "A_A") (pintype "passive"))
      (node (ref "R1") (pin "1") (pinfunction "1_1") (pintype "passive"))
    )
    (net (code "22") (name "Net-(RC14-Pad1)") (class "Default")
      (node (ref "RC14") (pin "1") (pinfunction "1_1") (pintype "passive"))
      (node (ref "RC17") (pin "1") (pinfunction "1_1") (pintype "passive"))
    )
    (net (code "23") (name "Net-(RC20-Pad2)") (class "Default")
      (node (ref "RC20") (pin "2") (pinfunction "2_2") (pintype "passive"))
      (node (ref "RC21") (pin "1") (pinfunction "1_1") (pintype "passive"))
    )
    (net (code "24") (name "Net-(RC21-Pad2)") (class "Default")
      (node (ref "RC21") (pin "2") (pinfunction "2_2") (pintype "passive"))
      (node (ref "RC22") (pin "1") (pinfunction "1_1") (pintype "passive"))
    )
    (net (code "25") (name "Net-(RD14-Pad1)") (class "Default")
      (node (ref "RD14") (pin "1") (pinfunction "1_1") (pintype "passive"))
      (node (ref "RD17") (pin "1") (pinfunction "1_1") (pintype "passive"))
    )
    (net (code "26") (name "Net-(RD20-Pad2)") (class "Default")
      (node (ref "RD20") (pin "2") (pinfunction "2_2") (pintype "passive"))
      (node (ref "RD21") (pin "1") (pinfunction "1_1") (pintype "passive"))
    )
    (net (code "27") (name "Net-(RD21-Pad2)") (class "Default")
      (node (ref "RD21") (pin "2") (pinfunction "2_2") (pintype "passive"))
      (node (ref "RD22") (pin "1") (pinfunction "1_1") (pintype "passive"))
    )
    (net (code "28") (name "Net-(S1-VI+)") (class "Default")
      (node (ref "L1") (pin "2") (pinfunction "2_2") (pintype "passive"))
      (node (ref "S1") (pin "IP") (pinfunction "VI+_IP") (pintype "passive"))
    )
    (net (code "29") (name "Net-(S1-VI-)") (class "Default")
      (node (ref "0Vin") (pin "1") (pinfunction "1_1") (pintype "passive"))
      (node (ref "C1") (pin "1") (pinfunction "1_1") (pintype "passive"))
      (node (ref "LED1") (pin "K") (pinfunction "K_K") (pintype "passive"))
      (node (ref "S1") (pin "IM") (pinfunction "VI-_IM") (pintype "passive"))
    )
    (net (code "30") (name "Net-(S1-VO+)") (class "Default")
      (node (ref "L2") (pin "1") (pinfunction "1_1") (pintype "passive"))
      (node (ref "S1") (pin "OP") (pinfunction "VO+_OP") (pintype "passive"))
    )
    (net (code "31") (name "Net-(S1-VO-)") (class "Default")
      (node (ref "L3") (pin "1") (pinfunction "1_1") (pintype "passive"))
      (node (ref "S1") (pin "OM") (pinfunction "VO-_OM") (pintype "passive"))
    )
    (net (code "32") (name "Net-(U7-Vout)") (class "Default")
      (node (ref "C5") (pin "2") (pinfunction "2_2") (pintype "passive"))
      (node (ref "U7") (pin "3") (pinfunction "Vout_3") (pintype "passive"))
      (node (ref "U8") (pin "1") (pinfunction "VDD1_1") (pintype "passive"))
      (node (ref "U9") (pin "8") (pinfunction "VDD2_8") (pintype "passive"))
      (node (ref "UC6") (pin "1") (pinfunction "Vref_1") (pintype "passive"))
      (node (ref "UC6") (pin "8") (pinfunction "Vcc_8") (pintype "passive"))
      (node (ref "UD6") (pin "1") (pinfunction "Vref_1") (pintype "passive"))
      (node (ref "UD6") (pin "8") (pinfunction "Vcc_8") (pintype "passive"))
    )
    (net (code "33") (name "Net-(U8-GND2)") (class "Default")
      (node (ref "U8") (pin "5") (pinfunction "GND2_5") (pintype "passive"))
      (node (ref "U9") (pin "4") (pinfunction "GND1_4") (pintype "passive"))
      (node (ref "V0") (pin "1") (pinfunction "1_1") (pintype "passive"))
    )
    (net (code "34") (name "Net-(U8-VDD2)") (class "Default")
      (node (ref "U8") (pin "8") (pinfunction "VDD2_8") (pintype "passive"))
      (node (ref "U9") (pin "1") (pinfunction "VDD1_1") (pintype "passive"))
      (node (ref "Vdd") (pin "1") (pinfunction "1_1") (pintype "passive"))
    )
    (net (code "35") (name "Net-(U8-VIA)") (class "Default")
      (node (ref "SCK") (pin "1") (pinfunction "1_1") (pintype "passive"))
      (node (ref "U8") (pin "7") (pinfunction "VIA_7") (pintype "passive"))
    )
    (net (code "36") (name "Net-(U8-VIB)") (class "Default")
      (node (ref "U8") (pin "3") (pinfunction "VIB_3") (pintype "passive"))
      (node (ref "UC6") (pin "6") (pinfunction "SDO_6") (pintype "passive"))
      (node (ref "UD6") (pin "6") (pinfunction "SDO_6") (pintype "passive"))
    )
    (net (code "37") (name "Net-(U8-VOA)") (class "Default")
      (node (ref "U8") (pin "2") (pinfunction "VOA_2") (pintype "passive"))
      (node (ref "UC6") (pin "7") (pinfunction "SCK_7") (pintype "passive"))
      (node (ref "UD6") (pin "7") (pinfunction "SCK_7") (pintype "passive"))
    )
    (net (code "38") (name "Net-(U8-VOB)") (class "Default")
      (node (ref "SDO") (pin "1") (pinfunction "1_1") (pintype "passive"))
      (node (ref "U8") (pin "6") (pinfunction "VOB_6") (pintype "passive"))
    )
    (net (code "39") (name "Net-(U9-VIA)") (class "Default")
      (node (ref "COMP1") (pin "1") (pinfunction "1_1") (pintype "passive"))
      (node (ref "U9") (pin "2") (pinfunction "VIA_2") (pintype "passive"))
    )
    (net (code "40") (name "Net-(U9-VIB)") (class "Default")
      (node (ref "COMP2") (pin "1") (pinfunction "1_1") (pintype "passive"))
      (node (ref "U9") (pin "3") (pinfunction "VIB_3") (pintype "passive"))
    )
    (net (code "41") (name "Net-(U9-VOA)") (class "Default")
      (node (ref "U9") (pin "7") (pinfunction "VOA_7") (pintype "passive"))
      (node (ref "UC6") (pin "5") (pinfunction "CONV_5") (pintype "passive"))
    )
    (net (code "42") (name "Net-(U9-VOB)") (class "Default")
      (node (ref "U9") (pin "6") (pinfunction "VOB_6") (pintype "passive"))
      (node (ref "UD6") (pin "5") (pinfunction "CONV_5") (pintype "passive"))
    )
    (net (code "43") (name "Net-(UA1-IN+)") (class "Default")
      (node (ref "INA") (pin "1") (pinfunction "1_1") (pintype "passive"))
      (node (ref "RA3") (pin "2") (pinfunction "2_2") (pintype "passive"))
      (node (ref "UA1") (pin "3") (pinfunction "IN+_3") (pintype "passive"))
    )
    (net (code "44") (name "Net-(UA1-IN-)") (class "Default")
      (node (ref "RA1") (pin "2") (pinfunction "2_2") (pintype "passive"))
      (node (ref "RA2") (pin "1") (pinfunction "1_1") (pintype "passive"))
      (node (ref "UA1") (pin "2") (pinfunction "IN-_2") (pintype "passive"))
    )
    (net (code "45") (name "Net-(UA1-OUT)") (class "Default")
      (node (ref "OUTA") (pin "1") (pinfunction "1_1") (pintype "passive"))
      (node (ref "RA2") (pin "2") (pinfunction "2_2") (pintype "passive"))
      (node (ref "UA1") (pin "6") (pinfunction "OUT_6") (pintype "passive"))
    )
    (net (code "46") (name "Net-(UB1-IN+)") (class "Default")
      (node (ref "INB") (pin "1") (pinfunction "1_1") (pintype "passive"))
      (node (ref "RB3") (pin "2") (pinfunction "2_2") (pintype "passive"))
      (node (ref "UB1") (pin "3") (pinfunction "IN+_3") (pintype "passive"))
    )
    (net (code "47") (name "Net-(UB1-IN-)") (class "Default")
      (node (ref "RB1") (pin "2") (pinfunction "2_2") (pintype "passive"))
      (node (ref "RB2") (pin "1") (pinfunction "1_1") (pintype "passive"))
      (node (ref "UB1") (pin "2") (pinfunction "IN-_2") (pintype "passive"))
    )
    (net (code "48") (name "Net-(UB1-OUT)") (class "Default")
      (node (ref "OUTB") (pin "1") (pinfunction "1_1") (pintype "passive"))
      (node (ref "RB2") (pin "2") (pinfunction "2_2") (pintype "passive"))
      (node (ref "UB1") (pin "6") (pinfunction "OUT_6") (pintype "passive"))
    )
    (net (code "49") (name "Net-(UC1-IN+)") (class "Default")
      (node (ref "INC") (pin "1") (pinfunction "1_1") (pintype "passive"))
      (node (ref "UC1") (pin "3") (pinfunction "IN+_3") (pintype "passive"))
    )
    (net (code "50") (name "Net-(UC1-IN-)") (class "Default")
      (node (ref "CC6") (pin "1") (pinfunction "1_1") (pintype "passive"))
      (node (ref "UC1") (pin "2") (pinfunction "IN-_2") (pintype "passive"))
      (node (ref "UC1") (pin "6") (pinfunction "OUT_6") (pintype "passive"))
    )
    (net (code "51") (name "Net-(UC2-AO+)") (class "Default")
      (node (ref "CC6") (pin "2") (pinfunction "2_2") (pintype "passive"))
      (node (ref "RC3") (pin "2") (pinfunction "2_2") (pintype "passive"))
      (node (ref "UC2") (pin "5") (pinfunction "AO+_5") (pintype "passive"))
    )
    (net (code "52") (name "Net-(UC2-AO-)") (class "Default")
      (node (ref "RC1") (pin "2") (pinfunction "2_2") (pintype "passive"))
      (node (ref "RC2") (pin "2") (pinfunction "2_2") (pintype "passive"))
      (node (ref "UC2") (pin "6") (pinfunction "AO-_6") (pintype "passive"))
    )
    (net (code "53") (name "Net-(UC2-AOo)") (class "Default")
      (node (ref "RC2") (pin "1") (pinfunction "1_1") (pintype "passive"))
      (node (ref "UC2") (pin "3") (pinfunction "Vin3_3") (pintype "passive"))
      (node (ref "UC2") (pin "7") (pinfunction "AOo_7") (pintype "passive"))
    )
    (net (code "54") (name "Net-(UC2-BPo)") (class "Default")
      (node (ref "RC9") (pin "1") (pinfunction "1_1") (pintype "passive"))
      (node (ref "UC2") (pin "8") (pinfunction "BPo_8") (pintype "passive"))
      (node (ref "UC3") (pin "3") (pinfunction "Vin3_3") (pintype "passive"))
    )
    (net (code "55") (name "Net-(UC2-FA1)") (class "Default")
      (node (ref "RC8") (pin "1") (pinfunction "1_1") (pintype "passive"))
      (node (ref "UC2") (pin "9") (pinfunction "FA1_9") (pintype "passive"))
    )
    (net (code "56") (name "Net-(UC2-FA2)") (class "Default")
      (node (ref "RC9") (pin "2") (pinfunction "2_2") (pintype "passive"))
      (node (ref "UC2") (pin "16") (pinfunction "FA2_16") (pintype "passive"))
    )
    (net (code "57") (name "Net-(UC2-HPo)") (class "Default")
      (node (ref "RC24") (pin "1") (pinfunction "1_1") (pintype "passive"))
      (node (ref "RC8") (pin "2") (pinfunction "2_2") (pintype "passive"))
      (node (ref "UC2") (pin "14") (pinfunction "HPo_14") (pintype "passive"))
    )
    (net (code "58") (name "Net-(UC2-Vin1)") (class "Default")
      (node (ref "RC24") (pin "2") (pinfunction "2_2") (pintype "passive"))
      (node (ref "UC2") (pin "13") (pinfunction "Vin1_13") (pintype "passive"))
    )
    (net (code "59") (name "Net-(UC2-Vin2)") (class "Default")
      (node (ref "RC4") (pin "2") (pinfunction "2_2") (pintype "passive"))
      (node (ref "UC2") (pin "4") (pinfunction "Vin2_4") (pintype "passive"))
    )
    (net (code "60") (name "Net-(UC3-AO+)") (class "Default")
      (node (ref "RC7") (pin "1") (pinfunction "1_1") (pintype "passive"))
      (node (ref "UC3") (pin "5") (pinfunction "AO+_5") (pintype "passive"))
      (node (ref "UC3") (pin "8") (pinfunction "BPo_8") (pintype "passive"))
    )
    (net (code "61") (name "Net-(UC3-AO-)") (class "Default")
      (node (ref "RC25") (pin "1") (pinfunction "1_1") (pintype "passive"))
      (node (ref "RC26") (pin "2") (pinfunction "2_2") (pintype "passive"))
      (node (ref "UC3") (pin "6") (pinfunction "AO-_6") (pintype "passive"))
    )
    (net (code "62") (name "Net-(UC3-AOo)") (class "Default")
      (node (ref "CC9") (pin "1") (pinfunction "1_1") (pintype "passive"))
      (node (ref "RC12") (pin "2") (pinfunction "2_2") (pintype "passive"))
      (node (ref "RC25") (pin "3") (pinfunction "3_3") (pintype "passive"))
      (node (ref "UC3") (pin "7") (pinfunction "AOo_7") (pintype "passive"))
    )
    (net (code "63") (name "Net-(UC3-FA1)") (class "Default")
      (node (ref "RC6") (pin "1") (pinfunction "1_1") (pintype "passive"))
      (node (ref "UC3") (pin "9") (pinfunction "FA1_9") (pintype "passive"))
    )
    (net (code "64") (name "Net-(UC3-FA2)") (class "Default")
      (node (ref "RC7") (pin "2") (pinfunction "2_2") (pintype "passive"))
      (node (ref "UC3") (pin "16") (pinfunction "FA2_16") (pintype "passive"))
    )
    (net (code "65") (name "Net-(UC3-HPo)") (class "Default")
      (node (ref "RC27") (pin "1") (pinfunction "1_1") (pintype "passive"))
      (node (ref "RC6") (pin "2") (pinfunction "2_2") (pintype "passive"))
      (node (ref "UC3") (pin "14") (pinfunction "HPo_14") (pintype "passive"))
    )
    (net (code "66") (name "Net-(UC3-Vin1)") (class "Default")
      (node (ref "RC27") (pin "2") (pinfunction "2_2") (pintype "passive"))
      (node (ref "UC3") (pin "13") (pinfunction "Vin1_13") (pintype "passive"))
    )
    (net (code "67") (name "Net-(UC3-Vin2)") (class "Default")
      (node (ref "RC5") (pin "2") (pinfunction "2_2") (pintype "passive"))
      (node (ref "UC3") (pin "4") (pinfunction "Vin2_4") (pintype "passive"))
    )
    (net (code "68") (name "Net-(UC4-IN+)") (class "Default")
      (node (ref "CC10") (pin "2") (pinfunction "2_2") (pintype "passive"))
      (node (ref "RC13") (pin "1") (pinfunction "1_1") (pintype "passive"))
      (node (ref "UC4") (pin "3") (pinfunction "IN+_3") (pintype "passive"))
    )
    (net (code "69") (name "Net-(UC4-IN-)") (class "Default")
      (node (ref "CC14") (pin "1") (pinfunction "1_1") (pintype "passive"))
      (node (ref "UC4") (pin "2") (pinfunction "IN-_2") (pintype "passive"))
      (node (ref "UC4") (pin "6") (pinfunction "OUT_6") (pintype "passive"))
    )
    (net (code "70") (name "Net-(UC5-INA+)") (class "Default")
      (node (ref "RC16") (pin "2") (pinfunction "2_2") (pintype "passive"))
      (node (ref "UC5") (pin "3") (pinfunction "INA+_3") (pintype "passive"))
    )
    (net (code "71") (name "Net-(UC5-INA-)") (class "Default")
      (node (ref "RC14") (pin "2") (pinfunction "2_2") (pintype "passive"))
      (node (ref "RC15") (pin "2") (pinfunction "2_2") (pintype "passive"))
      (node (ref "RC15") (pin "3") (pinfunction "3_3") (pintype "passive"))
      (node (ref "UC5") (pin "2") (pinfunction "INA-_2") (pintype "passive"))
    )
    (net (code "72") (name "Net-(UC5-INB+)") (class "Default")
      (node (ref "RC21") (pin "3") (pinfunction "3_3") (pintype "passive"))
      (node (ref "UC5") (pin "5") (pinfunction "INB+_5") (pintype "passive"))
    )
    (net (code "73") (name "Net-(UC5-INB-)") (class "Default")
      (node (ref "RC18") (pin "2") (pinfunction "2_2") (pintype "passive"))
      (node (ref "RC19") (pin "2") (pinfunction "2_2") (pintype "passive"))
      (node (ref "RC19") (pin "3") (pinfunction "3_3") (pintype "passive"))
      (node (ref "UC5") (pin "6") (pinfunction "INB-_6") (pintype "passive"))
    )
    (net (code "74") (name "Net-(UC5-OUTA)") (class "Default")
      (node (ref "Analog1") (pin "1") (pinfunction "1_1") (pintype "passive"))
      (node (ref "RC17") (pin "2") (pinfunction "2_2") (pintype "passive"))
      (node (ref "RC17") (pin "3") (pinfunction "3_3") (pintype "passive"))
      (node (ref "RC18") (pin "1") (pinfunction "1_1") (pintype "passive"))
      (node (ref "UC5") (pin "1") (pinfunction "OUTA_1") (pintype "passive"))
    )
    (net (code "75") (name "Net-(UC5-OUTB)") (class "Default")
      (node (ref "RC19") (pin "1") (pinfunction "1_1") (pintype "passive"))
      (node (ref "RC23") (pin "1") (pinfunction "1_1") (pintype "passive"))
      (node (ref "UC5") (pin "7") (pinfunction "OUTB_7") (pintype "passive"))
    )
    (net (code "76") (name "Net-(UC6-IN+)") (class "Default")
      (node (ref "DC1") (pin "K") (pinfunction "K_K") (pintype "passive"))
      (node (ref "RC23") (pin "2") (pinfunction "2_2") (pintype "passive"))
      (node (ref "UC6") (pin "2") (pinfunction "IN+_2") (pintype "passive"))
    )
    (net (code "77") (name "Net-(UD1-IN+)") (class "Default")
      (node (ref "IND") (pin "1") (pinfunction "1_1") (pintype "passive"))
      (node (ref "UD1") (pin "3") (pinfunction "IN+_3") (pintype "passive"))
    )
    (net (code "78") (name "Net-(UD1-IN-)") (class "Default")
      (node (ref "CD6") (pin "1") (pinfunction "1_1") (pintype "passive"))
      (node (ref "UD1") (pin "2") (pinfunction "IN-_2") (pintype "passive"))
      (node (ref "UD1") (pin "6") (pinfunction "OUT_6") (pintype "passive"))
    )
    (net (code "79") (name "Net-(UD2-AO+)") (class "Default")
      (node (ref "CD6") (pin "2") (pinfunction "2_2") (pintype "passive"))
      (node (ref "RD3") (pin "2") (pinfunction "2_2") (pintype "passive"))
      (node (ref "UD2") (pin "5") (pinfunction "AO+_5") (pintype "passive"))
    )
    (net (code "80") (name "Net-(UD2-AO-)") (class "Default")
      (node (ref "RD1") (pin "2") (pinfunction "2_2") (pintype "passive"))
      (node (ref "RD2") (pin "2") (pinfunction "2_2") (pintype "passive"))
      (node (ref "UD2") (pin "6") (pinfunction "AO-_6") (pintype "passive"))
    )
    (net (code "81") (name "Net-(UD2-AOo)") (class "Default")
      (node (ref "RD2") (pin "1") (pinfunction "1_1") (pintype "passive"))
      (node (ref "UD2") (pin "3") (pinfunction "Vin3_3") (pintype "passive"))
      (node (ref "UD2") (pin "7") (pinfunction "AOo_7") (pintype "passive"))
    )
    (net (code "82") (name "Net-(UD2-BPo)") (class "Default")
      (node (ref "RD9") (pin "1") (pinfunction "1_1") (pintype "passive"))
      (node (ref "UD2") (pin "8") (pinfunction "BPo_8") (pintype "passive"))
      (node (ref "UD3") (pin "3") (pinfunction "Vin3_3") (pintype "passive"))
    )
    (net (code "83") (name "Net-(UD2-FA1)") (class "Default")
      (node (ref "RD8") (pin "1") (pinfunction "1_1") (pintype "passive"))
      (node (ref "UD2") (pin "9") (pinfunction "FA1_9") (pintype "passive"))
    )
    (net (code "84") (name "Net-(UD2-FA2)") (class "Default")
      (node (ref "RD9") (pin "2") (pinfunction "2_2") (pintype "passive"))
      (node (ref "UD2") (pin "16") (pinfunction "FA2_16") (pintype "passive"))
    )
    (net (code "85") (name "Net-(UD2-HPo)") (class "Default")
      (node (ref "RD24") (pin "1") (pinfunction "1_1") (pintype "passive"))
      (node (ref "RD8") (pin "2") (pinfunction "2_2") (pintype "passive"))
      (node (ref "UD2") (pin "14") (pinfunction "HPo_14") (pintype "passive"))
    )
    (net (code "86") (name "Net-(UD2-Vin1)") (class "Default")
      (node (ref "RD24") (pin "2") (pinfunction "2_2") (pintype "passive"))
      (node (ref "UD2") (pin "13") (pinfunction "Vin1_13") (pintype "passive"))
    )
    (net (code "87") (name "Net-(UD2-Vin2)") (class "Default")
      (node (ref "RD4") (pin "2") (pinfunction "2_2") (pintype "passive"))
      (node (ref "UD2") (pin "4") (pinfunction "Vin2_4") (pintype "passive"))
    )
    (net (code "88") (name "Net-(UD3-AO+)") (class "Default")
      (node (ref "RD7") (pin "1") (pinfunction "1_1") (pintype "passive"))
      (node (ref "UD3") (pin "5") (pinfunction "AO+_5") (pintype "passive"))
      (node (ref "UD3") (pin "8") (pinfunction "BPo_8") (pintype "passive"))
    )
    (net (code "89") (name "Net-(UD3-AO-)") (class "Default")
      (node (ref "RD25") (pin "1") (pinfunction "1_1") (pintype "passive"))
      (node (ref "RD26") (pin "2") (pinfunction "2_2") (pintype "passive"))
      (node (ref "UD3") (pin "6") (pinfunction "AO-_6") (pintype "passive"))
    )
    (net (code "90") (name "Net-(UD3-AOo)") (class "Default")
      (node (ref "CD9") (pin "1") (pinfunction "1_1") (pintype "passive"))
      (node (ref "RD12") (pin "2") (pinfunction "2_2") (pintype "passive"))
      (node (ref "RD25") (pin "3") (pinfunction "3_3") (pintype "passive"))
      (node (ref "UD3") (pin "7") (pinfunction "AOo_7") (pintype "passive"))
    )
    (net (code "91") (name "Net-(UD3-FA1)") (class "Default")
      (node (ref "RD6") (pin "1") (pinfunction "1_1") (pintype "passive"))
      (node (ref "UD3") (pin "9") (pinfunction "FA1_9") (pintype "passive"))
    )
    (net (code "92") (name "Net-(UD3-FA2)") (class "Default")
      (node (ref "RD7") (pin "2") (pinfunction "2_2") (pintype "passive"))
      (node (ref "UD3") (pin "16") (pinfunction "FA2_16") (pintype "passive"))
    )
    (net (code "93") (name "Net-(UD3-HPo)") (class "Default")
      (node (ref "RD27") (pin "1") (pinfunction "1_1") (pintype "passive"))
      (node (ref "RD6") (pin "2") (pinfunction "2_2") (pintype "passive"))
      (node (ref "UD3") (pin "14") (pinfunction "HPo_14") (pintype "passive"))
    )
    (net (code "94") (name "Net-(UD3-Vin1)") (class "Default")
      (node (ref "RD27") (pin "2") (pinfunction "2_2") (pintype "passive"))
      (node (ref "UD3") (pin "13") (pinfunction "Vin1_13") (pintype "passive"))
    )
    (net (code "95") (name "Net-(UD3-Vin2)") (class "Default")
      (node (ref "RD5") (pin "2") (pinfunction "2_2") (pintype "passive"))
      (node (ref "UD3") (pin "4") (pinfunction "Vin2_4") (pintype "passive"))
    )
    (net (code "96") (name "Net-(UD4-IN+)") (class "Default")
      (node (ref "CD10") (pin "2") (pinfunction "2_2") (pintype "passive"))
      (node (ref "RD13") (pin "1") (pinfunction "1_1") (pintype "passive"))
      (node (ref "UD4") (pin "3") (pinfunction "IN+_3") (pintype "passive"))
    )
    (net (code "97") (name "Net-(UD4-IN-)") (class "Default")
      (node (ref "CD14") (pin "1") (pinfunction "1_1") (pintype "passive"))
      (node (ref "UD4") (pin "2") (pinfunction "IN-_2") (pintype "passive"))
      (node (ref "UD4") (pin "6") (pinfunction "OUT_6") (pintype "passive"))
    )
    (net (code "98") (name "Net-(UD5-INA+)") (class "Default")
      (node (ref "RD16") (pin "2") (pinfunction "2_2") (pintype "passive"))
      (node (ref "UD5") (pin "3") (pinfunction "INA+_3") (pintype "passive"))
    )
    (net (code "99") (name "Net-(UD5-INA-)") (class "Default")
      (node (ref "RD14") (pin "2") (pinfunction "2_2") (pintype "passive"))
      (node (ref "RD15") (pin "2") (pinfunction "2_2") (pintype "passive"))
      (node (ref "RD15") (pin "3") (pinfunction "3_3") (pintype "passive"))
      (node (ref "UD5") (pin "2") (pinfunction "INA-_2") (pintype "passive"))
    )
    (net (code "100") (name "Net-(UD5-INB+)") (class "Default")
      (node (ref "RD21") (pin "3") (pinfunction "3_3") (pintype "passive"))
      (node (ref "UD5") (pin "5") (pinfunction "INB+_5") (pintype "passive"))
    )
    (net (code "101") (name "Net-(UD5-INB-)") (class "Default")
      (node (ref "RD18") (pin "2") (pinfunction "2_2") (pintype "passive"))
      (node (ref "RD19") (pin "2") (pinfunction "2_2") (pintype "passive"))
      (node (ref "RD19") (pin "3") (pinfunction "3_3") (pintype "passive"))
      (node (ref "UD5") (pin "6") (pinfunction "INB-_6") (pintype "passive"))
    )
    (net (code "102") (name "Net-(UD5-OUTA)") (class "Default")
      (node (ref "Analog2") (pin "1") (pinfunction "1_1") (pintype "passive"))
      (node (ref "RD17") (pin "2") (pinfunction "2_2") (pintype "passive"))
      (node (ref "RD17") (pin "3") (pinfunction "3_3") (pintype "passive"))
      (node (ref "RD18") (pin "1") (pinfunction "1_1") (pintype "passive"))
      (node (ref "UD5") (pin "1") (pinfunction "OUTA_1") (pintype "passive"))
    )
    (net (code "103") (name "Net-(UD5-OUTB)") (class "Default")
      (node (ref "RD19") (pin "1") (pinfunction "1_1") (pintype "passive"))
      (node (ref "RD23") (pin "1") (pinfunction "1_1") (pintype "passive"))
      (node (ref "UD5") (pin "7") (pinfunction "OUTB_7") (pintype "passive"))
    )
    (net (code "104") (name "Net-(UD6-IN+)") (class "Default")
      (node (ref "DD1") (pin "K") (pinfunction "K_K") (pintype "passive"))
      (node (ref "RD23") (pin "2") (pinfunction "2_2") (pintype "passive"))
      (node (ref "UD6") (pin "2") (pinfunction "IN+_2") (pintype "passive"))
    )
    (net (code "105") (name "unconnected-(M1-Pad1)") (class "Default")
      (node (ref "M1") (pin "1") (pinfunction "1_1") (pintype "passive"))
    )
    (net (code "106") (name "unconnected-(M2-Pad1)") (class "Default")
      (node (ref "M2") (pin "1") (pinfunction "1_1") (pintype "passive"))
    )
    (net (code "107") (name "unconnected-(M3-Pad1)") (class "Default")
      (node (ref "M3") (pin "1") (pinfunction "1_1") (pintype "passive"))
    )
    (net (code "108") (name "unconnected-(M4-Pad1)") (class "Default")
      (node (ref "M4") (pin "1") (pinfunction "1_1") (pintype "passive"))
    )
    (net (code "109") (name "unconnected-(RC25-Pad2)") (class "Default")
      (node (ref "RC25") (pin "2") (pinfunction "2_2") (pintype "passive"))
    )
    (net (code "110") (name "unconnected-(RD25-Pad2)") (class "Default")
      (node (ref "RD25") (pin "2") (pinfunction "2_2") (pintype "passive"))
    )
    (net (code "111") (name "unconnected-(UC2-LPo-Pad1)") (class "Default")
      (node (ref "UC2") (pin "1") (pinfunction "LPo_1") (pintype "passive"))
    )
    (net (code "112") (name "unconnected-(UC3-LPo-Pad1)") (class "Default")
      (node (ref "UC3") (pin "1") (pinfunction "LPo_1") (pintype "passive"))
    )
    (net (code "113") (name "unconnected-(UD2-LPo-Pad1)") (class "Default")
      (node (ref "UD2") (pin "1") (pinfunction "LPo_1") (pintype "passive"))
    )
    (net (code "114") (name "unconnected-(UD3-LPo-Pad1)") (class "Default")
      (node (ref "UD3") (pin "1") (pinfunction "LPo_1") (pintype "passive"))
    )
  )
)
